# power.net
KiCad netlist of a schematic drawn in Altium Designer
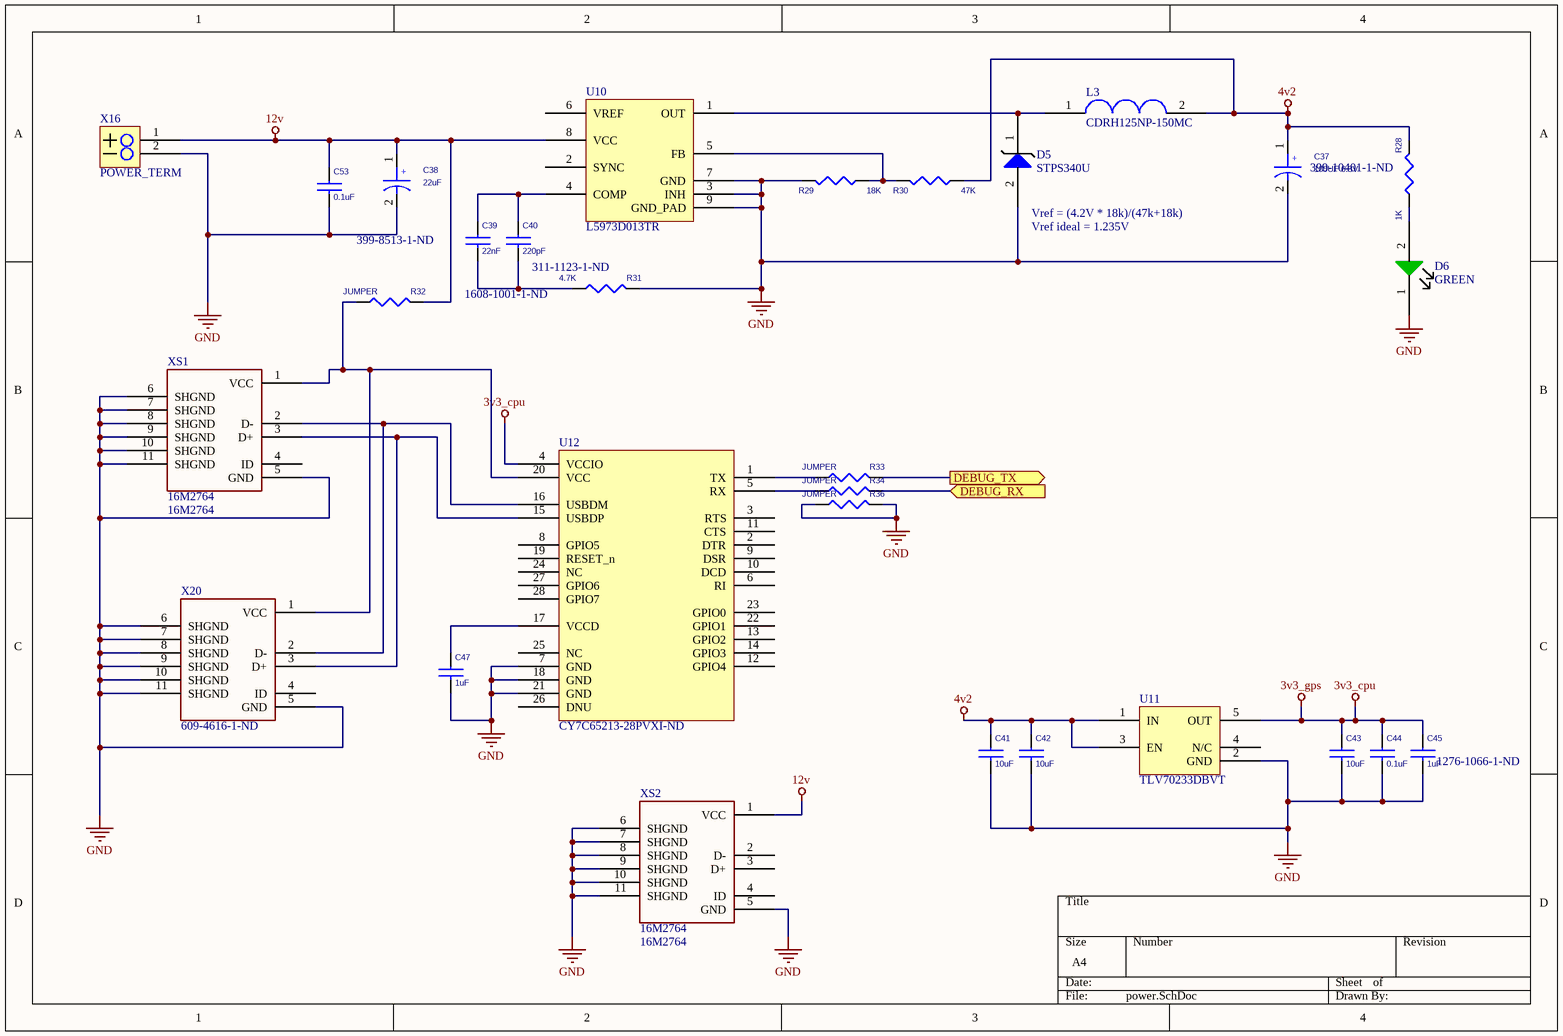
[diagram p0: power.SchDoc]

(export (version "E")
  (design (tool "Eeschema 10.0.6"))
  (components
    (comp (ref "C37")
      (value "100UF 6.3V")
      (footprint "CAPMP6133X31N")
      (description "CAP 100uF; 6.3V; Case: C; ESR:150mOhm")
      (fields (field (name "SUPPLIER PART NUMBER 1") "399-10401-1-ND"))
      (libsource (lib "Capacitors") (part "CAP_SMD_100UF_10%"))
    )
    (comp (ref "C38")
      (value "22uF")
      (footprint "CAPMP7143X31N")
      (description "CAP SMD 35volts 22uF 10% ESR=300mOhms")
      (fields (field (name "SUPPLIER PART NUMBER 1") "399-8513-1-ND"))
      (libsource (lib "Capacitors") (part "CAP_SMD_22UF_10%"))
    )
    (comp (ref "C39")
      (value "22nF")
      (footprint "CAPC2012X09M")
      (description "CAP 22NF 50V 10% X7R 0805")
      (fields (field (name "SUPPLIER PART NUMBER 1") "1608-1001-1-ND"))
      (libsource (lib "Capacitors") (part "CAP_SMD_22nF_10%"))
    )
    (comp (ref "C40")
      (value "220pF")
      (footprint "CAPC2012X09M")
      (description "CAP 220PF 50V 10%  0805")
      (fields (field (name "SUPPLIER PART NUMBER 1") "311-1123-1-ND"))
      (libsource (lib "Capacitors") (part "CAP_SMD_220pF_10%"))
    )
    (comp (ref "C41")
      (value "10uF")
      (footprint "CAPC2012X09M")
      (description "CAP CER 10UF 16V 20% X5R 0805")
      (libsource (lib "Capacitors") (part "CAP_SMD_10UF_20%"))
    )
    (comp (ref "C42")
      (value "10uF")
      (footprint "CAPC2012X09M")
      (description "CAP CER 10UF 16V 20% X5R 0805")
      (libsource (lib "Capacitors") (part "CAP_SMD_10UF_20%"))
    )
    (comp (ref "C43")
      (value "10uF")
      (footprint "CAPC2012X09M")
      (description "CAP CER 10UF 16V 20% X5R 0805")
      (libsource (lib "Capacitors") (part "CAP_SMD_10UF_20%"))
    )
    (comp (ref "C44")
      (value "0.1uF")
      (footprint "CAPC2012X09M")
      (description "CAP CER 0.1UF 25V 10% X7R 0805")
      (libsource (lib "Capacitors") (part "CAP_SMD_0.1UF_10%"))
    )
    (comp (ref "C45")
      (value "1uF")
      (footprint "CAPC2012X09M")
      (description "MLCC; 1uF; 25V; X7R; ±10%; SMD; 0805;")
      (fields (field (name "SUPPLIER PART NUMBER 1") "1276-1066-1-ND"))
      (libsource (lib "Capacitors") (part "CAP_SMD_1uF_10%"))
    )
    (comp (ref "C47")
      (value "1uF")
      (footprint "CAPC2012X09M")
      (description "MLCC; 1uF; 25V; X7R; ±10%; SMD; 0805;")
      (libsource (lib "Capacitors") (part "CAP_SMD_1uF_10%"))
    )
    (comp (ref "C53")
      (value "0.1uF")
      (footprint "CAPC2012X09M")
      (description "CAP CER 0.1UF 25V 10% X7R 0805")
      (libsource (lib "Capacitors") (part "CAP_SMD_0.1UF_10%"))
    )
    (comp (ref "D5")
      (value "STPS340U")
      (footprint "SODFL535X265-2N")
      (description "DIODE, ZENER, 20V, 3W")
      (libsource (lib "Passive") (part "STPS340U"))
    )
    (comp (ref "D6")
      (value "GREEN")
      (footprint "DIOC2012X11N")
      (libsource (lib "Passive") (part "LED_GREEN"))
    )
    (comp (ref "L3")
      (value "CDRH125NP-150MC")
      (footprint "INDP123123X40N_SUMIDA")
      (libsource (lib "Passive") (part "IND_15uH_3.3A"))
    )
    (comp (ref "R28")
      (value "1K")
      (footprint "RESC2013X06M")
      (description "RES - 1K OHM, 5%, 1/8W, 0805 SMD")
      (libsource (lib "Resistors") (part "RES_SMD_1K_5%"))
    )
    (comp (ref "R29")
      (value "18K")
      (footprint "RESC2013X06M")
      (description "RES 18K OHM 1/8W 1% 0805 SMD")
      (libsource (lib "Resistors") (part "RES_SMD_18K_1%"))
    )
    (comp (ref "R30")
      (value "47K")
      (footprint "RESC2013X06M")
      (description "RES 47K OHM 1/8W 1% 0805")
      (libsource (lib "Resistors") (part "RES_SMD_47K_1%"))
    )
    (comp (ref "R31")
      (value "4.7K")
      (footprint "RESC2013X06M")
      (description "RES 4.7K OHM 1/8W 1% 0805 SMD")
      (libsource (lib "Resistors") (part "RES_SMD_4.7K_1%"))
    )
    (comp (ref "R32")
      (value "JUMPER")
      (footprint "RESC2013X06M_CMEASURE")
      (description "RES 0.0 OHM 1/8W JUMP 0805 SMD")
      (libsource (lib "Resistors") (part "RES_SMD_0_CURRENT"))
    )
    (comp (ref "R33")
      (value "JUMPER")
      (footprint "RESC2013X06M_CMEASURE")
      (description "RES 0.0 OHM 1/8W JUMP 0805 SMD")
      (libsource (lib "Resistors") (part "RES_SMD_0_CURRENT"))
    )
    (comp (ref "R34")
      (value "JUMPER")
      (footprint "RESC2013X06M_CMEASURE")
      (description "RES 0.0 OHM 1/8W JUMP 0805 SMD")
      (libsource (lib "Resistors") (part "RES_SMD_0_CURRENT"))
    )
    (comp (ref "R36")
      (value "JUMPER")
      (footprint "RESC2013X06M_CMEASURE")
      (description "RES 0.0 OHM 1/8W JUMP 0805 SMD")
      (libsource (lib "Resistors") (part "RES_SMD_0_CURRENT"))
    )
    (comp (ref "U10")
      (value "L5973D013TR")
      (footprint "SOIC127P600X175_HS-9N")
      (description "IC REG BUCK ADJ 2.5A SOIC8")
      (libsource (lib "TruthEar") (part "L5973D013TR"))
    )
    (comp (ref "U11")
      (value "TLV70233DBVT")
      (footprint "SOT95P280X145-5M")
      (libsource (lib "TruthEar") (part "TLV70233DBVT"))
    )
    (comp (ref "U12")
      (value "CY7C65213")
      (footprint "SOP65P780X200-28M")
      (fields (field (name "SUPPLIER PART NUMBER 1") "CY7C65213-28PVXI-ND"))
      (libsource (lib "TruthEar") (part "CY7C65213"))
    )
    (comp (ref "X16")
      (value "POWER_TERM")
      (footprint "PH5")
      (libsource (lib "Connectors") (part "POWER_TERM"))
    )
    (comp (ref "X20")
      (value "10118193-0001LF")
      (footprint "USB_MICRO_10118193")
      (fields (field (name "SUPPLIER PART NUMBER 1") "609-4616-1-ND"))
      (libsource (lib "Connectors") (part "USB_MICRO"))
    )
    (comp (ref "XS1")
      (value "16M2764")
      (footprint "USB_MINI_16M2764")
      (fields (field (name "SUPPLIER PART NUMBER 1") "16M2764"))
      (libsource (lib "Connectors") (part "USB_MINI_16M2764"))
    )
    (comp (ref "XS2")
      (value "16M2764")
      (footprint "USB_MINI_16M2764")
      (fields (field (name "SUPPLIER PART NUMBER 1") "16M2764"))
      (libsource (lib "Connectors") (part "USB_MINI_16M2764"))
    )
  )
  (nets
    (net (code "1") (name "/DEBUG_RX") (class "Default")
      (node (ref "R34") (pin "2") (pinfunction "2_2") (pintype "passive"))
    )
    (net (code "2") (name "/DEBUG_TX") (class "Default")
      (node (ref "R33") (pin "2") (pinfunction "2_2") (pintype "passive"))
    )
    (net (code "3") (name "3v3_cpu") (class "Default")
      (node (ref "C43") (pin "1") (pinfunction "1_1") (pintype "passive"))
      (node (ref "C44") (pin "1") (pinfunction "1_1") (pintype "passive"))
      (node (ref "C45") (pin "1") (pinfunction "1_1") (pintype "passive"))
      (node (ref "U11") (pin "5") (pinfunction "OUT_5") (pintype "passive"))
      (node (ref "U12") (pin "4") (pinfunction "VCCIO_4") (pintype "power_in"))
    )
    (net (code "4") (name "4v2") (class "Default")
      (node (ref "C37") (pin "1") (pinfunction "1_1") (pintype "passive"))
      (node (ref "C41") (pin "1") (pinfunction "1_1") (pintype "passive"))
      (node (ref "C42") (pin "1") (pinfunction "1_1") (pintype "passive"))
      (node (ref "L3") (pin "2") (pinfunction "2_2") (pintype "passive"))
      (node (ref "R28") (pin "2") (pinfunction "2_2") (pintype "passive"))
      (node (ref "R30") (pin "1") (pinfunction "1_1") (pintype "passive"))
      (node (ref "U11") (pin "1") (pinfunction "IN_1") (pintype "passive"))
      (node (ref "U11") (pin "3") (pinfunction "EN_3") (pintype "passive"))
    )
    (net (code "5") (name "12v") (class "Default")
      (node (ref "C38") (pin "1") (pinfunction "1_1") (pintype "passive"))
      (node (ref "C53") (pin "1") (pinfunction "1_1") (pintype "passive"))
      (node (ref "R32") (pin "2") (pinfunction "2_2") (pintype "passive"))
      (node (ref "U10") (pin "8") (pinfunction "VCC_8") (pintype "passive"))
      (node (ref "X16") (pin "1") (pinfunction "1_1") (pintype "passive"))
      (node (ref "XS2") (pin "1") (pinfunction "VCC_1") (pintype "passive"))
    )
    (net (code "6") (name "GND") (class "Default")
      (node (ref "C37") (pin "2") (pinfunction "2_2") (pintype "passive"))
      (node (ref "C38") (pin "2") (pinfunction "2_2") (pintype "passive"))
      (node (ref "C41") (pin "2") (pinfunction "2_2") (pintype "passive"))
      (node (ref "C42") (pin "2") (pinfunction "2_2") (pintype "passive"))
      (node (ref "C43") (pin "2") (pinfunction "2_2") (pintype "passive"))
      (node (ref "C44") (pin "2") (pinfunction "2_2") (pintype "passive"))
      (node (ref "C45") (pin "2") (pinfunction "2_2") (pintype "passive"))
      (node (ref "C47") (pin "2") (pinfunction "2_2") (pintype "passive"))
      (node (ref "C53") (pin "2") (pinfunction "2_2") (pintype "passive"))
      (node (ref "D5") (pin "2") (pinfunction "A_2") (pintype "passive"))
      (node (ref "D6") (pin "1") (pinfunction "C_1") (pintype "passive"))
      (node (ref "R29") (pin "2") (pinfunction "2_2") (pintype "passive"))
      (node (ref "R31") (pin "2") (pinfunction "2_2") (pintype "passive"))
      (node (ref "R36") (pin "1") (pinfunction "1_1") (pintype "passive"))
      (node (ref "R36") (pin "2") (pinfunction "2_2") (pintype "passive"))
      (node (ref "U10") (pin "3") (pinfunction "INH_3") (pintype "passive"))
      (node (ref "U10") (pin "7") (pinfunction "GND_7") (pintype "passive"))
      (node (ref "U10") (pin "9") (pinfunction "GND_PAD_9") (pintype "passive"))
      (node (ref "U11") (pin "2") (pinfunction "GND_2") (pintype "passive"))
      (node (ref "U12") (pin "18") (pinfunction "GND_18") (pintype "power_in"))
      (node (ref "U12") (pin "21") (pinfunction "GND_21") (pintype "power_in"))
      (node (ref "U12") (pin "7") (pinfunction "GND_7") (pintype "power_in"))
      (node (ref "X16") (pin "2") (pinfunction "2_2") (pintype "passive"))
      (node (ref "X20") (pin "10") (pinfunction "SHGND_10") (pintype "passive"))
      (node (ref "X20") (pin "11") (pinfunction "SHGND_11") (pintype "passive"))
      (node (ref "X20") (pin "5") (pinfunction "GND_5") (pintype "passive"))
      (node (ref "X20") (pin "6") (pinfunction "SHGND_6") (pintype "passive"))
      (node (ref "X20") (pin "7") (pinfunction "SHGND_7") (pintype "passive"))
      (node (ref "X20") (pin "8") (pinfunction "SHGND_8") (pintype "passive"))
      (node (ref "X20") (pin "9") (pinfunction "SHGND_9") (pintype "passive"))
      (node (ref "XS1") (pin "10") (pinfunction "SHGND_10") (pintype "passive"))
      (node (ref "XS1") (pin "11") (pinfunction "SHGND_11") (pintype "passive"))
      (node (ref "XS1") (pin "5") (pinfunction "GND_5") (pintype "passive"))
      (node (ref "XS1") (pin "6") (pinfunction "SHGND_6") (pintype "passive"))
      (node (ref "XS1") (pin "7") (pinfunction "SHGND_7") (pintype "passive"))
      (node (ref "XS1") (pin "8") (pinfunction "SHGND_8") (pintype "passive"))
      (node (ref "XS1") (pin "9") (pinfunction "SHGND_9") (pintype "passive"))
      (node (ref "XS2") (pin "10") (pinfunction "SHGND_10") (pintype "passive"))
      (node (ref "XS2") (pin "11") (pinfunction "SHGND_11") (pintype "passive"))
      (node (ref "XS2") (pin "5") (pinfunction "GND_5") (pintype "passive"))
      (node (ref "XS2") (pin "6") (pinfunction "SHGND_6") (pintype "passive"))
      (node (ref "XS2") (pin "7") (pinfunction "SHGND_7") (pintype "passive"))
      (node (ref "XS2") (pin "8") (pinfunction "SHGND_8") (pintype "passive"))
      (node (ref "XS2") (pin "9") (pinfunction "SHGND_9") (pintype "passive"))
    )
    (net (code "7") (name "Net-(C39-Pad2)") (class "Default")
      (node (ref "C39") (pin "2") (pinfunction "2_2") (pintype "passive"))
      (node (ref "C40") (pin "2") (pinfunction "2_2") (pintype "passive"))
      (node (ref "R31") (pin "1") (pinfunction "1_1") (pintype "passive"))
    )
    (net (code "8") (name "Net-(D5-C)") (class "Default")
      (node (ref "D5") (pin "1") (pinfunction "C_1") (pintype "passive"))
      (node (ref "L3") (pin "1") (pinfunction "1_1") (pintype "passive"))
      (node (ref "U10") (pin "1") (pinfunction "OUT_1") (pintype "passive"))
    )
    (net (code "9") (name "Net-(D6-A)") (class "Default")
      (node (ref "D6") (pin "2") (pinfunction "A_2") (pintype "passive"))
      (node (ref "R28") (pin "1") (pinfunction "1_1") (pintype "passive"))
    )
    (net (code "10") (name "Net-(U10-COMP)") (class "Default")
      (node (ref "C39") (pin "1") (pinfunction "1_1") (pintype "passive"))
      (node (ref "C40") (pin "1") (pinfunction "1_1") (pintype "passive"))
      (node (ref "U10") (pin "4") (pinfunction "COMP_4") (pintype "passive"))
    )
    (net (code "11") (name "Net-(U10-FB)") (class "Default")
      (node (ref "R29") (pin "1") (pinfunction "1_1") (pintype "passive"))
      (node (ref "R30") (pin "2") (pinfunction "2_2") (pintype "passive"))
      (node (ref "U10") (pin "5") (pinfunction "FB_5") (pintype "passive"))
    )
    (net (code "12") (name "Net-(U12-RX)") (class "Default")
      (node (ref "R34") (pin "1") (pinfunction "1_1") (pintype "passive"))
      (node (ref "U12") (pin "5") (pinfunction "RX_5") (pintype "power_in"))
    )
    (net (code "13") (name "Net-(U12-TX)") (class "Default")
      (node (ref "R33") (pin "1") (pinfunction "1_1") (pintype "passive"))
      (node (ref "U12") (pin "1") (pinfunction "TX_1") (pintype "power_in"))
    )
    (net (code "14") (name "Net-(U12-USBDM)") (class "Default")
      (node (ref "U12") (pin "16") (pinfunction "USBDM_16") (pintype "power_in"))
      (node (ref "X20") (pin "2") (pinfunction "D-_2") (pintype "passive"))
      (node (ref "XS1") (pin "2") (pinfunction "D-_2") (pintype "passive"))
    )
    (net (code "15") (name "Net-(U12-USBDP)") (class "Default")
      (node (ref "U12") (pin "15") (pinfunction "USBDP_15") (pintype "power_in"))
      (node (ref "X20") (pin "3") (pinfunction "D+_3") (pintype "passive"))
      (node (ref "XS1") (pin "3") (pinfunction "D+_3") (pintype "passive"))
    )
    (net (code "16") (name "Net-(U12-VCC)") (class "Default")
      (node (ref "R32") (pin "1") (pinfunction "1_1") (pintype "passive"))
      (node (ref "U12") (pin "20") (pinfunction "VCC_20") (pintype "power_in"))
      (node (ref "X20") (pin "1") (pinfunction "VCC_1") (pintype "passive"))
      (node (ref "XS1") (pin "1") (pinfunction "VCC_1") (pintype "passive"))
    )
    (net (code "17") (name "Net-(U12-VCCD)") (class "Default")
      (node (ref "C47") (pin "1") (pinfunction "1_1") (pintype "passive"))
      (node (ref "U12") (pin "17") (pinfunction "VCCD_17") (pintype "power_in"))
    )
    (net (code "18") (name "unconnected-(U10-SYNC-Pad2)") (class "Default")
      (node (ref "U10") (pin "2") (pinfunction "SYNC_2") (pintype "passive"))
    )
    (net (code "19") (name "unconnected-(U10-VREF-Pad6)") (class "Default")
      (node (ref "U10") (pin "6") (pinfunction "VREF_6") (pintype "passive"))
    )
    (net (code "20") (name "unconnected-(U11-N{slash}C-Pad4)") (class "Default")
      (node (ref "U11") (pin "4") (pinfunction "N/C_4") (pintype "passive"))
    )
    (net (code "21") (name "unconnected-(U12-CTS-Pad11)") (class "Default")
      (node (ref "U12") (pin "11") (pinfunction "CTS_11") (pintype "power_in"))
    )
    (net (code "22") (name "unconnected-(U12-DCD-Pad10)") (class "Default")
      (node (ref "U12") (pin "10") (pinfunction "DCD_10") (pintype "power_in"))
    )
    (net (code "23") (name "unconnected-(U12-DNU-Pad26)") (class "Default")
      (node (ref "U12") (pin "26") (pinfunction "DNU_26") (pintype "power_in"))
    )
    (net (code "24") (name "unconnected-(U12-DSR-Pad9)") (class "Default")
      (node (ref "U12") (pin "9") (pinfunction "DSR_9") (pintype "power_in"))
    )
    (net (code "25") (name "unconnected-(U12-DTR-Pad2)") (class "Default")
      (node (ref "U12") (pin "2") (pinfunction "DTR_2") (pintype "power_in"))
    )
    (net (code "26") (name "unconnected-(U12-GPIO0-Pad23)") (class "Default")
      (node (ref "U12") (pin "23") (pinfunction "GPIO0_23") (pintype "power_in"))
    )
    (net (code "27") (name "unconnected-(U12-GPIO1-Pad22)") (class "Default")
      (node (ref "U12") (pin "22") (pinfunction "GPIO1_22") (pintype "power_in"))
    )
    (net (code "28") (name "unconnected-(U12-GPIO2-Pad13)") (class "Default")
      (node (ref "U12") (pin "13") (pinfunction "GPIO2_13") (pintype "power_in"))
    )
    (net (code "29") (name "unconnected-(U12-GPIO3-Pad14)") (class "Default")
      (node (ref "U12") (pin "14") (pinfunction "GPIO3_14") (pintype "power_in"))
    )
    (net (code "30") (name "unconnected-(U12-GPIO4-Pad12)") (class "Default")
      (node (ref "U12") (pin "12") (pinfunction "GPIO4_12") (pintype "power_in"))
    )
    (net (code "31") (name "unconnected-(U12-GPIO5-Pad8)") (class "Default")
      (node (ref "U12") (pin "8") (pinfunction "GPIO5_8") (pintype "power_in"))
    )
    (net (code "32") (name "unconnected-(U12-GPIO6-Pad27)") (class "Default")
      (node (ref "U12") (pin "27") (pinfunction "GPIO6_27") (pintype "power_in"))
    )
    (net (code "33") (name "unconnected-(U12-GPIO7-Pad28)") (class "Default")
      (node (ref "U12") (pin "28") (pinfunction "GPIO7_28") (pintype "power_in"))
    )
    (net (code "34") (name "unconnected-(U12-NC-Pad24)") (class "Default")
      (node (ref "U12") (pin "24") (pinfunction "NC_24") (pintype "power_in"))
    )
    (net (code "35") (name "unconnected-(U12-NC-Pad25)") (class "Default")
      (node (ref "U12") (pin "25") (pinfunction "NC_25") (pintype "power_in"))
    )
    (net (code "36") (name "unconnected-(U12-RESET_n-Pad19)") (class "Default")
      (node (ref "U12") (pin "19") (pinfunction "RESET_n_19") (pintype "power_in"))
    )
    (net (code "37") (name "unconnected-(U12-RI-Pad6)") (class "Default")
      (node (ref "U12") (pin "6") (pinfunction "RI_6") (pintype "power_in"))
    )
    (net (code "38") (name "unconnected-(U12-RTS-Pad3)") (class "Default")
      (node (ref "U12") (pin "3") (pinfunction "RTS_3") (pintype "power_in"))
    )
    (net (code "39") (name "unconnected-(X20-ID-Pad4)") (class "Default")
      (node (ref "X20") (pin "4") (pinfunction "ID_4") (pintype "passive"))
    )
    (net (code "40") (name "unconnected-(XS1-ID-Pad4)") (class "Default")
      (node (ref "XS1") (pin "4") (pinfunction "ID_4") (pintype "passive"))
    )
    (net (code "41") (name "unconnected-(XS2-D+-Pad3)") (class "Default")
      (node (ref "XS2") (pin "3") (pinfunction "D+_3") (pintype "passive"))
    )
    (net (code "42") (name "unconnected-(XS2-D--Pad2)") (class "Default")
      (node (ref "XS2") (pin "2") (pinfunction "D-_2") (pintype "passive"))
    )
    (net (code "43") (name "unconnected-(XS2-ID-Pad4)") (class "Default")
      (node (ref "XS2") (pin "4") (pinfunction "ID_4") (pintype "passive"))
    )
  )
)
